# TDA2003-Amplifier-Mono.net
KiCad netlist of a schematic drawn in EAGLE
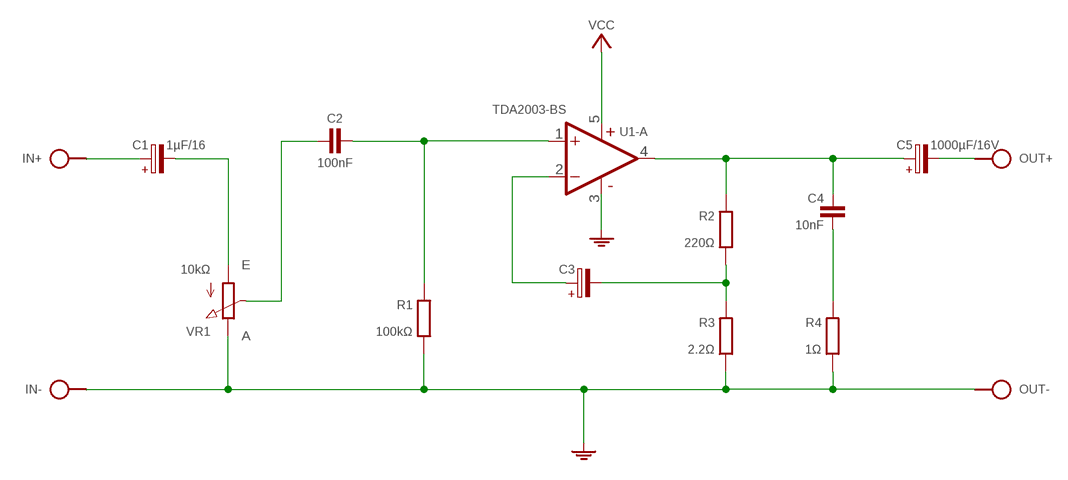
[diagram p0: schematic, sheet 1]

(export (version "E")
  (design (tool "Eeschema 10.0.6"))
  (components
    (comp (ref "C1")
      (value "1µF/16")
      (footprint "eagle-import:E2,5-3")
      (libsource (lib "eagle-import") (part "CPOL-HE2,5-3"))
    )
    (comp (ref "C2")
      (value "100nF")
      (footprint "eagle-import:C050-020X044")
      (libsource (lib "eagle-import") (part "C-H050-020X044"))
    )
    (comp (ref "C3")
      (value "CPOL-HE5-4")
      (footprint "eagle-import:E5-4")
      (libsource (lib "eagle-import") (part "CPOL-HE5-4"))
    )
    (comp (ref "C4")
      (value "10nF")
      (footprint "eagle-import:C050-020X044_V")
      (libsource (lib "eagle-import") (part "C050-020X044/V"))
    )
    (comp (ref "C5")
      (value "1000µF/16V")
      (footprint "eagle-import:E5-5")
      (libsource (lib "eagle-import") (part "CPOL-HE5-5"))
    )
    (comp (ref "IN")
      (value "SPAD+--+")
      (footprint "eagle-import:SPAD-+")
      (libsource (lib "eagle-import") (part "SPAD+--+"))
    )
    (comp (ref "OUT")
      (value "SPAD+--+")
      (footprint "eagle-import:SPAD-+")
      (libsource (lib "eagle-import") (part "SPAD+--+"))
    )
    (comp (ref "PWR")
      (value "VCC_GNDL")
      (footprint "eagle-import:SPAD-+")
      (libsource (lib "eagle-import") (part "VCC_GNDL"))
    )
    (comp (ref "R1")
      (value "100kΩ")
      (footprint "eagle-import:0204_2")
      (libsource (lib "eagle-import") (part "R0204/2"))
    )
    (comp (ref "R2")
      (value "220Ω")
      (footprint "eagle-import:0204_10-V")
      (libsource (lib "eagle-import") (part "R0204/10-V"))
    )
    (comp (ref "R3")
      (value "2.2Ω")
      (footprint "eagle-import:0204_10-V")
      (libsource (lib "eagle-import") (part "R0204/10-V"))
    )
    (comp (ref "R4")
      (value "1Ω")
      (footprint "eagle-import:0204_10-V")
      (libsource (lib "eagle-import") (part "R0204/10-V"))
    )
    (comp (ref "U1")
      (value "TDA2003-BS")
      (footprint "eagle-import:TO220-B5S")
      (libsource (lib "eagle-import") (part "TDA2003-BS"))
    )
    (comp (ref "VR1")
      (value "10kΩ")
      (footprint "eagle-import:CONN-3P")
      (libsource (lib "eagle-import") (part "POT-3P"))
    )
  )
  (nets
    (net (code "1") (name "GND") (class "Default")
      (node (ref "IN") (pin "1") (pinfunction "P$1_1") (pintype "passive"))
      (node (ref "OUT") (pin "1") (pinfunction "P$1_1") (pintype "passive"))
      (node (ref "PWR") (pin "1") (pinfunction "GND_1") (pintype "power_in"))
      (node (ref "R1") (pin "2") (pinfunction "1_2") (pintype "passive"))
      (node (ref "R3") (pin "2") (pinfunction "1_2") (pintype "passive"))
      (node (ref "R4") (pin "2") (pinfunction "1_2") (pintype "passive"))
      (node (ref "U1") (pin "3") (pinfunction "V-_3") (pintype "power_in"))
      (node (ref "VR1") (pin "3") (pinfunction "E_3") (pintype "passive"))
    )
    (net (code "2") (name "Net-(INA-P$1)") (class "Default")
      (node (ref "C1") (pin "+") (pinfunction "+_+") (pintype "passive"))
      (node (ref "IN") (pin "2") (pinfunction "P$1_2") (pintype "passive"))
    )
    (net (code "3") (name "Net-(OUTA-P$1)") (class "Default")
      (node (ref "C5") (pin "-") (pinfunction "-_-") (pintype "passive"))
      (node (ref "OUT") (pin "2") (pinfunction "P$1_2") (pintype "passive"))
    )
    (net (code "4") (name "Net-(PWRA-VCC)") (class "Default")
      (node (ref "PWR") (pin "2") (pinfunction "VCC_2") (pintype "power_in"))
      (node (ref "U1") (pin "5") (pinfunction "V+_5") (pintype "power_in"))
    )
    (net (code "5") (name "Net-(R1-2)") (class "Default")
      (node (ref "C2") (pin "2") (pinfunction "2_2") (pintype "passive"))
      (node (ref "R1") (pin "1") (pinfunction "2_1") (pintype "passive"))
      (node (ref "U1") (pin "1") (pinfunction "+IN_1") (pintype "input"))
    )
    (net (code "6") (name "Net-(R2-1)") (class "Default")
      (node (ref "C3") (pin "-") (pinfunction "-_-") (pintype "passive"))
      (node (ref "R2") (pin "2") (pinfunction "1_2") (pintype "passive"))
      (node (ref "R3") (pin "1") (pinfunction "2_1") (pintype "passive"))
    )
    (net (code "7") (name "Net-(R2-2)") (class "Default")
      (node (ref "C4") (pin "1") (pinfunction "1_1") (pintype "passive"))
      (node (ref "C5") (pin "+") (pinfunction "+_+") (pintype "passive"))
      (node (ref "R2") (pin "1") (pinfunction "2_1") (pintype "passive"))
      (node (ref "U1") (pin "4") (pinfunction "OUT_4") (pintype "output"))
    )
    (net (code "8") (name "Net-(R4-2)") (class "Default")
      (node (ref "C4") (pin "2") (pinfunction "2_2") (pintype "passive"))
      (node (ref "R4") (pin "1") (pinfunction "2_1") (pintype "passive"))
    )
    (net (code "9") (name "Net-(U1A--IN)") (class "Default")
      (node (ref "C3") (pin "+") (pinfunction "+_+") (pintype "passive"))
      (node (ref "U1") (pin "2") (pinfunction "-IN_2") (pintype "input"))
    )
    (net (code "10") (name "Net-(VR1-A)") (class "Default")
      (node (ref "C1") (pin "-") (pinfunction "-_-") (pintype "passive"))
      (node (ref "VR1") (pin "1") (pinfunction "A_1") (pintype "passive"))
    )
    (net (code "11") (name "Net-(VR1-S)") (class "Default")
      (node (ref "C2") (pin "1") (pinfunction "1_1") (pintype "passive"))
      (node (ref "VR1") (pin "2") (pinfunction "S_2") (pintype "passive"))
    )
  )
)
